# 17_FLOW_Sensor.net
KiCad netlist of a schematic drawn in Altium Designer
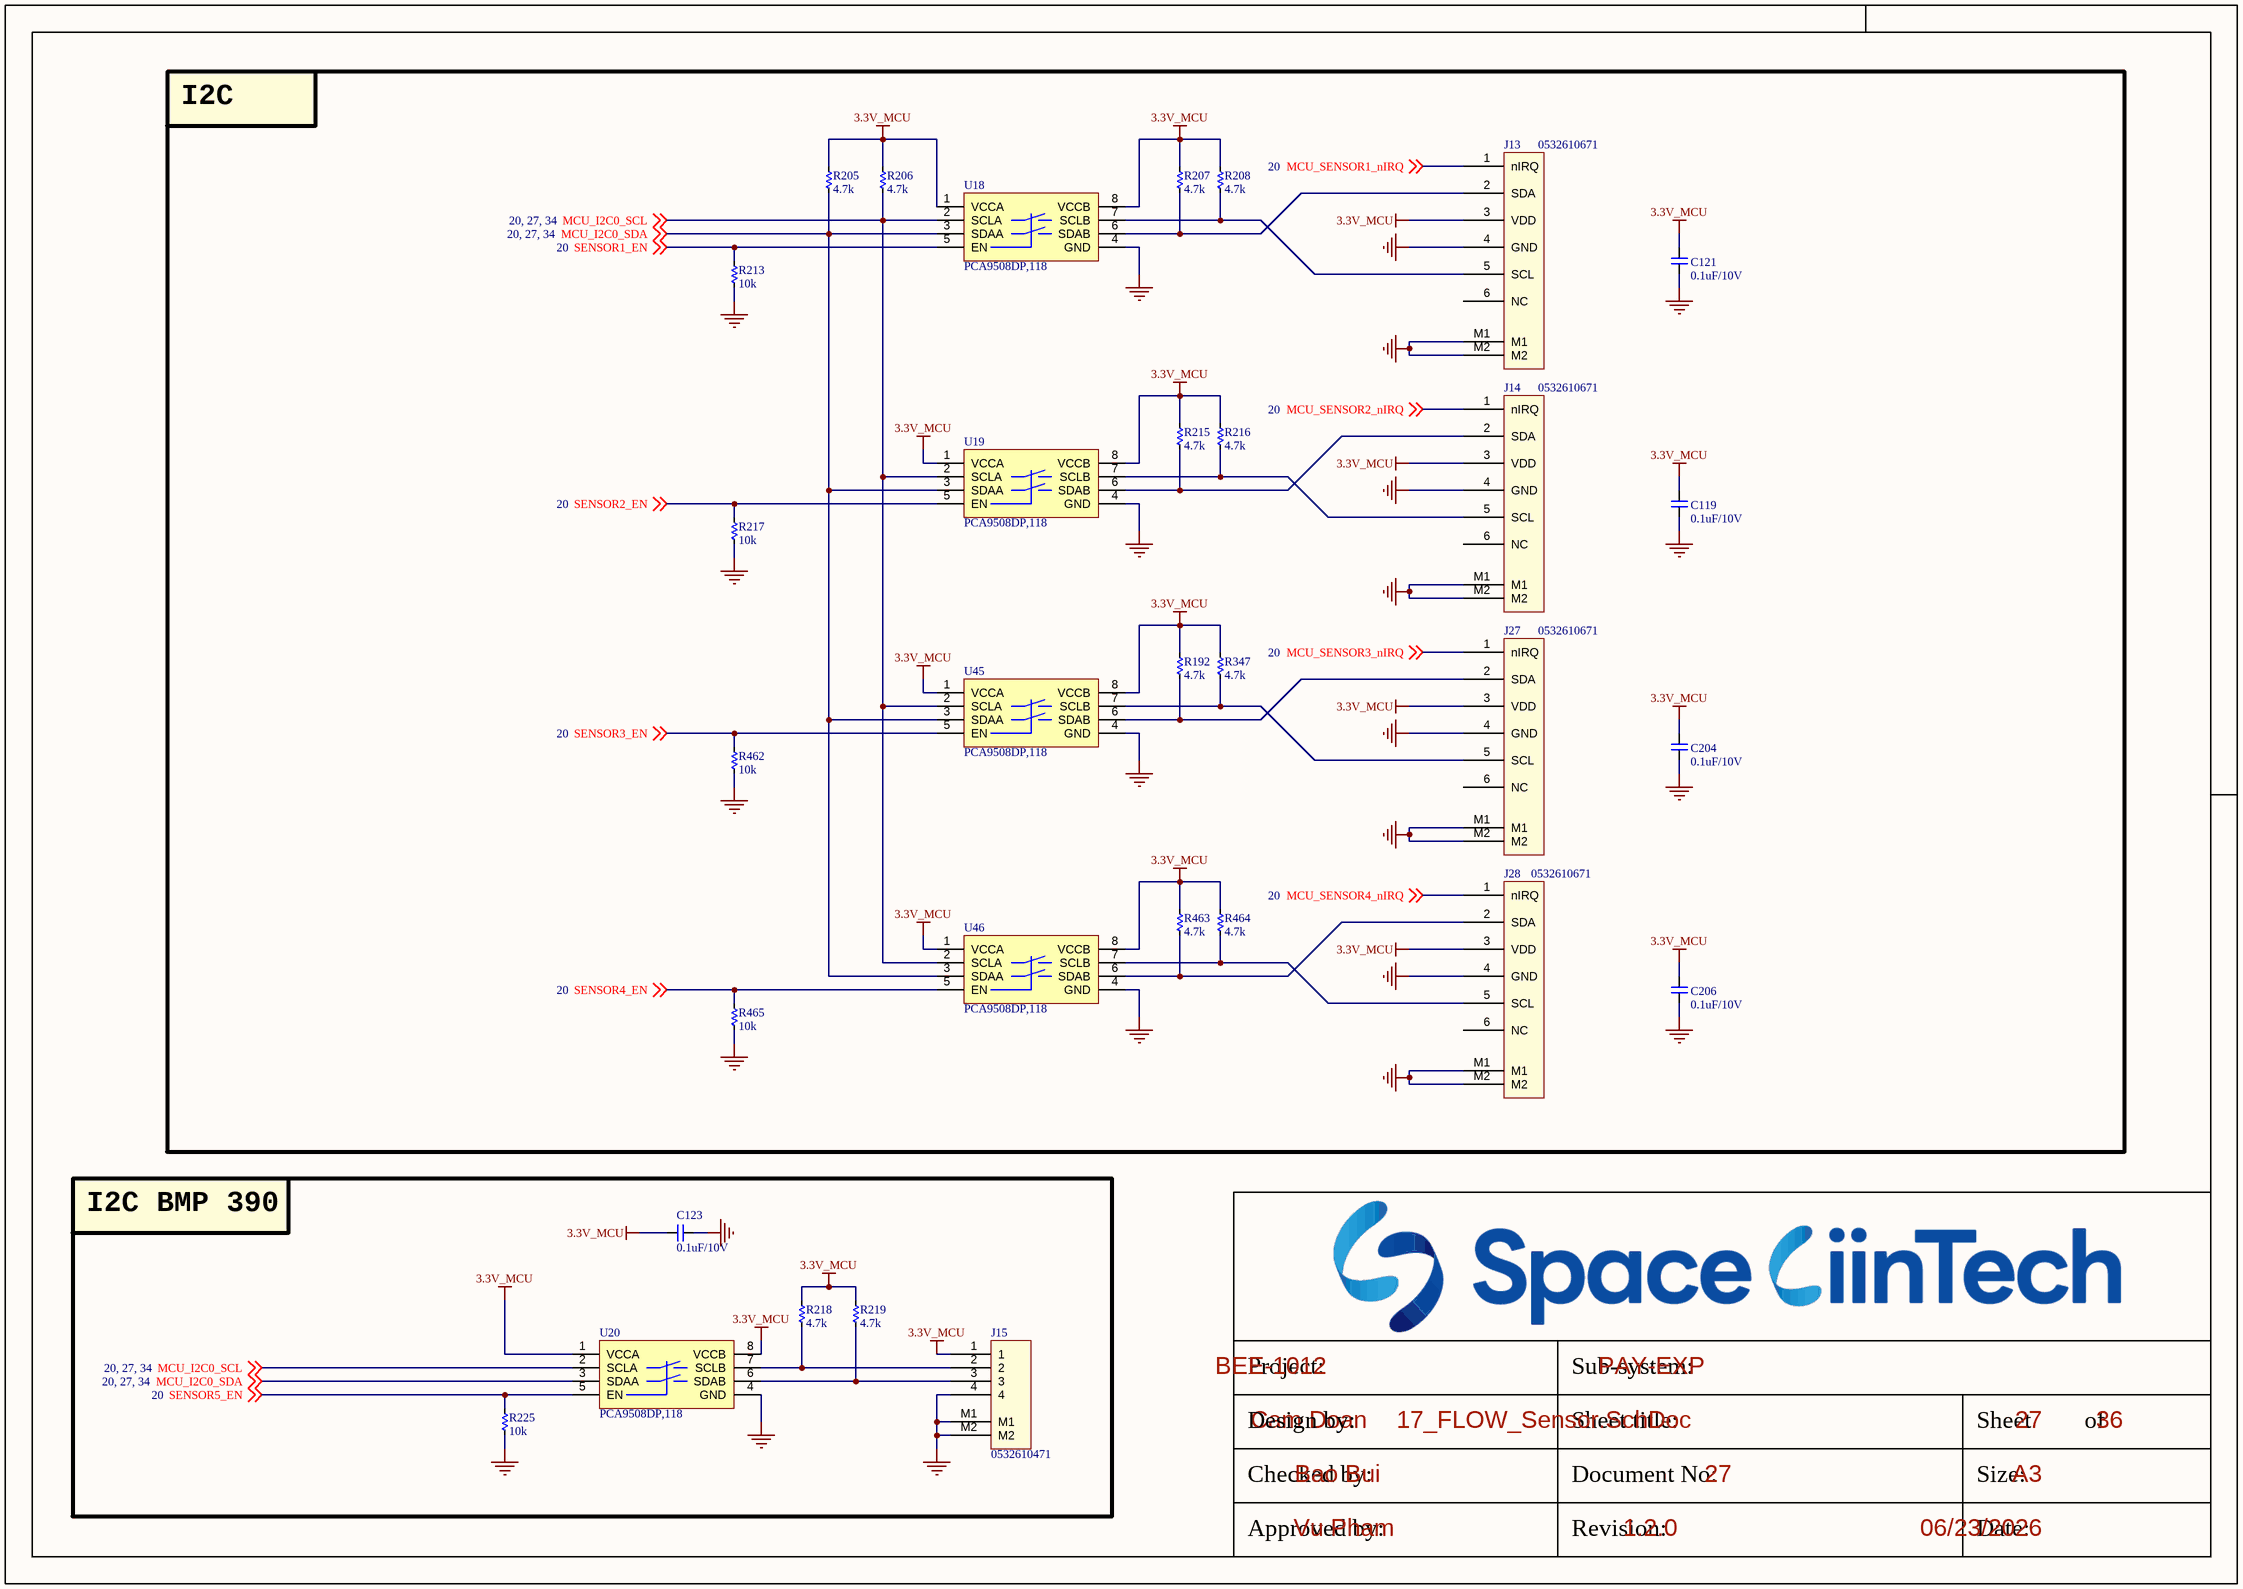
[diagram p0: 17_FLOW_Sensor.SchDoc]

(export (version "E")
  (design (tool "Eeschema 10.0.6"))
  (components
    (comp (ref "C119")
      (value "0.1uF/10V")
      (footprint "CAP_C_1005X60")
      (description "CAP")
      (libsource (lib "LABLIB") (part "_CAP_C_2"))
    )
    (comp (ref "C121")
      (value "0.1uF/10V")
      (footprint "CAP_C_1005X60")
      (description "CAP")
      (libsource (lib "LABLIB") (part "_CAP_C_2"))
    )
    (comp (ref "C123")
      (value "0.1uF/10V")
      (footprint "CAP_C_1005X60")
      (description "CAP")
      (libsource (lib "LABLIB") (part "_CAP_C_2"))
    )
    (comp (ref "C204")
      (value "0.1uF/10V")
      (footprint "CAP_C_1005X60")
      (description "CAP")
      (libsource (lib "LABLIB") (part "_CAP_C_2"))
    )
    (comp (ref "C206")
      (value "0.1uF/10V")
      (footprint "CAP_C_1005X60")
      (description "CAP")
      (libsource (lib "LABLIB") (part "_CAP_C_2"))
    )
    (comp (ref "J13")
      (value "0532610671")
      (footprint "MOLEX_0532610671")
      (libsource (lib "LABLIB") (part "FLOW_SENSOR"))
    )
    (comp (ref "J14")
      (value "0532610671")
      (footprint "MOLEX_0532610671")
      (libsource (lib "LABLIB") (part "FLOW_SENSOR"))
    )
    (comp (ref "J15")
      (value "0532610471")
      (footprint "MOLEX_0532610471")
      (libsource (lib "LABLIB") (part "Header 4x1_2M"))
    )
    (comp (ref "J27")
      (value "0532610671")
      (footprint "MOLEX_0532610671")
      (libsource (lib "LABLIB") (part "FLOW_SENSOR"))
    )
    (comp (ref "J28")
      (value "0532610671")
      (footprint "MOLEX_0532610671")
      (libsource (lib "LABLIB") (part "FLOW_SENSOR"))
    )
    (comp (ref "R192")
      (value "4.7k")
      (footprint "RES_C_1005X40")
      (description "RES")
      (libsource (lib "LABLIB") (part "_RES_B_2"))
    )
    (comp (ref "R205")
      (value "4.7k")
      (footprint "RES_C_1005X40")
      (description "RES")
      (libsource (lib "LABLIB") (part "_RES_B_2"))
    )
    (comp (ref "R206")
      (value "4.7k")
      (footprint "RES_C_1005X40")
      (description "RES")
      (libsource (lib "LABLIB") (part "_RES_B_2"))
    )
    (comp (ref "R207")
      (value "4.7k")
      (footprint "RES_C_1005X40")
      (description "RES")
      (libsource (lib "LABLIB") (part "_RES_B_2"))
    )
    (comp (ref "R208")
      (value "4.7k")
      (footprint "RES_C_1005X40")
      (description "RES")
      (libsource (lib "LABLIB") (part "_RES_B_2"))
    )
    (comp (ref "R213")
      (value "10k")
      (footprint "RES_C_1005X40")
      (description "RES")
      (libsource (lib "LABLIB") (part "_RES_B_2"))
    )
    (comp (ref "R215")
      (value "4.7k")
      (footprint "RES_C_1005X40")
      (description "RES")
      (libsource (lib "LABLIB") (part "_RES_B_2"))
    )
    (comp (ref "R216")
      (value "4.7k")
      (footprint "RES_C_1005X40")
      (description "RES")
      (libsource (lib "LABLIB") (part "_RES_B_2"))
    )
    (comp (ref "R217")
      (value "10k")
      (footprint "RES_C_1005X40")
      (description "RES")
      (libsource (lib "LABLIB") (part "_RES_B_2"))
    )
    (comp (ref "R218")
      (value "4.7k")
      (footprint "RES_C_1005X40")
      (description "RES")
      (libsource (lib "LABLIB") (part "_RES_B_2"))
    )
    (comp (ref "R219")
      (value "4.7k")
      (footprint "RES_C_1005X40")
      (description "RES")
      (libsource (lib "LABLIB") (part "_RES_B_2"))
    )
    (comp (ref "R225")
      (value "10k")
      (footprint "RES_C_1005X40")
      (description "RES")
      (libsource (lib "LABLIB") (part "_RES_B_2"))
    )
    (comp (ref "R347")
      (value "4.7k")
      (footprint "RES_C_1005X40")
      (description "RES")
      (libsource (lib "LABLIB") (part "_RES_B_2"))
    )
    (comp (ref "R462")
      (value "10k")
      (footprint "RES_C_1005X40")
      (description "RES")
      (libsource (lib "LABLIB") (part "_RES_B_2"))
    )
    (comp (ref "R463")
      (value "4.7k")
      (footprint "RES_C_1005X40")
      (description "RES")
      (libsource (lib "LABLIB") (part "_RES_B_2"))
    )
    (comp (ref "R464")
      (value "4.7k")
      (footprint "RES_C_1005X40")
      (description "RES")
      (libsource (lib "LABLIB") (part "_RES_B_2"))
    )
    (comp (ref "R465")
      (value "10k")
      (footprint "RES_C_1005X40")
      (description "RES")
      (libsource (lib "LABLIB") (part "_RES_B_2"))
    )
    (comp (ref "U18")
      (value "PCA9508DP,118")
      (footprint "TSOP8")
      (libsource (lib "EXP_HW_V3") (part "PCA9508DP,118"))
    )
    (comp (ref "U19")
      (value "PCA9508DP,118")
      (footprint "TSOP8")
      (libsource (lib "EXP_HW_V3") (part "PCA9508DP,118"))
    )
    (comp (ref "U20")
      (value "PCA9508DP,118")
      (footprint "TSOP8")
      (libsource (lib "EXP_HW_V3") (part "PCA9508DP,118"))
    )
    (comp (ref "U45")
      (value "PCA9508DP,118")
      (footprint "TSOP8")
      (libsource (lib "EXP_HW_V3") (part "PCA9508DP,118"))
    )
    (comp (ref "U46")
      (value "PCA9508DP,118")
      (footprint "TSOP8")
      (libsource (lib "EXP_HW_V3") (part "PCA9508DP,118"))
    )
  )
  (nets
    (net (code "1") (name "3.3V_MCU") (class "Default")
      (node (ref "C119") (pin "2") (pinfunction "2_2") (pintype "passive"))
      (node (ref "C121") (pin "2") (pinfunction "2_2") (pintype "passive"))
      (node (ref "C123") (pin "2") (pinfunction "2_2") (pintype "passive"))
      (node (ref "C204") (pin "2") (pinfunction "2_2") (pintype "passive"))
      (node (ref "C206") (pin "2") (pinfunction "2_2") (pintype "passive"))
      (node (ref "J13") (pin "3") (pinfunction "VDD_3") (pintype "passive"))
      (node (ref "J14") (pin "3") (pinfunction "VDD_3") (pintype "passive"))
      (node (ref "J15") (pin "1") (pinfunction "1_1") (pintype "passive"))
      (node (ref "J27") (pin "3") (pinfunction "VDD_3") (pintype "passive"))
      (node (ref "J28") (pin "3") (pinfunction "VDD_3") (pintype "passive"))
      (node (ref "R192") (pin "1") (pinfunction "1_1") (pintype "passive"))
      (node (ref "R205") (pin "1") (pinfunction "1_1") (pintype "passive"))
      (node (ref "R206") (pin "1") (pinfunction "1_1") (pintype "passive"))
      (node (ref "R207") (pin "1") (pinfunction "1_1") (pintype "passive"))
      (node (ref "R208") (pin "1") (pinfunction "1_1") (pintype "passive"))
      (node (ref "R215") (pin "1") (pinfunction "1_1") (pintype "passive"))
      (node (ref "R216") (pin "1") (pinfunction "1_1") (pintype "passive"))
      (node (ref "R218") (pin "1") (pinfunction "1_1") (pintype "passive"))
      (node (ref "R219") (pin "1") (pinfunction "1_1") (pintype "passive"))
      (node (ref "R347") (pin "1") (pinfunction "1_1") (pintype "passive"))
      (node (ref "R463") (pin "1") (pinfunction "1_1") (pintype "passive"))
      (node (ref "R464") (pin "1") (pinfunction "1_1") (pintype "passive"))
      (node (ref "U18") (pin "1") (pinfunction "VCCA_1") (pintype "passive"))
      (node (ref "U18") (pin "8") (pinfunction "VCCB_8") (pintype "passive"))
      (node (ref "U19") (pin "1") (pinfunction "VCCA_1") (pintype "passive"))
      (node (ref "U19") (pin "8") (pinfunction "VCCB_8") (pintype "passive"))
      (node (ref "U20") (pin "1") (pinfunction "VCCA_1") (pintype "passive"))
      (node (ref "U20") (pin "8") (pinfunction "VCCB_8") (pintype "passive"))
      (node (ref "U45") (pin "1") (pinfunction "VCCA_1") (pintype "passive"))
      (node (ref "U45") (pin "8") (pinfunction "VCCB_8") (pintype "passive"))
      (node (ref "U46") (pin "1") (pinfunction "VCCA_1") (pintype "passive"))
      (node (ref "U46") (pin "8") (pinfunction "VCCB_8") (pintype "passive"))
    )
    (net (code "2") (name "GND") (class "Default")
      (node (ref "C119") (pin "1") (pinfunction "1_1") (pintype "passive"))
      (node (ref "C121") (pin "1") (pinfunction "1_1") (pintype "passive"))
      (node (ref "C123") (pin "1") (pinfunction "1_1") (pintype "passive"))
      (node (ref "C204") (pin "1") (pinfunction "1_1") (pintype "passive"))
      (node (ref "C206") (pin "1") (pinfunction "1_1") (pintype "passive"))
      (node (ref "J13") (pin "4") (pinfunction "GND_4") (pintype "passive"))
      (node (ref "J13") (pin "M1") (pinfunction "M1_M1") (pintype "passive"))
      (node (ref "J13") (pin "M2") (pinfunction "M2_M2") (pintype "passive"))
      (node (ref "J14") (pin "4") (pinfunction "GND_4") (pintype "passive"))
      (node (ref "J14") (pin "M1") (pinfunction "M1_M1") (pintype "passive"))
      (node (ref "J14") (pin "M2") (pinfunction "M2_M2") (pintype "passive"))
      (node (ref "J15") (pin "4") (pinfunction "4_4") (pintype "passive"))
      (node (ref "J15") (pin "M1") (pinfunction "M1_M1") (pintype "passive"))
      (node (ref "J15") (pin "M2") (pinfunction "M2_M2") (pintype "passive"))
      (node (ref "J27") (pin "4") (pinfunction "GND_4") (pintype "passive"))
      (node (ref "J27") (pin "M1") (pinfunction "M1_M1") (pintype "passive"))
      (node (ref "J27") (pin "M2") (pinfunction "M2_M2") (pintype "passive"))
      (node (ref "J28") (pin "4") (pinfunction "GND_4") (pintype "passive"))
      (node (ref "J28") (pin "M1") (pinfunction "M1_M1") (pintype "passive"))
      (node (ref "J28") (pin "M2") (pinfunction "M2_M2") (pintype "passive"))
      (node (ref "R213") (pin "2") (pinfunction "2_2") (pintype "passive"))
      (node (ref "R217") (pin "2") (pinfunction "2_2") (pintype "passive"))
      (node (ref "R225") (pin "2") (pinfunction "2_2") (pintype "passive"))
      (node (ref "R462") (pin "2") (pinfunction "2_2") (pintype "passive"))
      (node (ref "R465") (pin "2") (pinfunction "2_2") (pintype "passive"))
      (node (ref "U18") (pin "4") (pinfunction "GND_4") (pintype "passive"))
      (node (ref "U19") (pin "4") (pinfunction "GND_4") (pintype "passive"))
      (node (ref "U20") (pin "4") (pinfunction "GND_4") (pintype "passive"))
      (node (ref "U45") (pin "4") (pinfunction "GND_4") (pintype "passive"))
      (node (ref "U46") (pin "4") (pinfunction "GND_4") (pintype "passive"))
    )
    (net (code "3") (name "MCU_I2C0_SCL") (class "Default")
      (node (ref "R206") (pin "2") (pinfunction "2_2") (pintype "passive"))
      (node (ref "U18") (pin "2") (pinfunction "SCLA_2") (pintype "passive"))
      (node (ref "U19") (pin "2") (pinfunction "SCLA_2") (pintype "passive"))
      (node (ref "U20") (pin "2") (pinfunction "SCLA_2") (pintype "passive"))
      (node (ref "U45") (pin "2") (pinfunction "SCLA_2") (pintype "passive"))
      (node (ref "U46") (pin "2") (pinfunction "SCLA_2") (pintype "passive"))
    )
    (net (code "4") (name "MCU_I2C0_SDA") (class "Default")
      (node (ref "R205") (pin "2") (pinfunction "2_2") (pintype "passive"))
      (node (ref "U18") (pin "3") (pinfunction "SDAA_3") (pintype "passive"))
      (node (ref "U19") (pin "3") (pinfunction "SDAA_3") (pintype "passive"))
      (node (ref "U20") (pin "3") (pinfunction "SDAA_3") (pintype "passive"))
      (node (ref "U45") (pin "3") (pinfunction "SDAA_3") (pintype "passive"))
      (node (ref "U46") (pin "3") (pinfunction "SDAA_3") (pintype "passive"))
    )
    (net (code "5") (name "MCU_SENSOR1_nIRQ") (class "Default")
      (node (ref "J13") (pin "1") (pinfunction "nIRQ_1") (pintype "passive"))
    )
    (net (code "6") (name "MCU_SENSOR2_nIRQ") (class "Default")
      (node (ref "J14") (pin "1") (pinfunction "nIRQ_1") (pintype "passive"))
    )
    (net (code "7") (name "MCU_SENSOR3_nIRQ") (class "Default")
      (node (ref "J27") (pin "1") (pinfunction "nIRQ_1") (pintype "passive"))
    )
    (net (code "8") (name "MCU_SENSOR4_nIRQ") (class "Default")
      (node (ref "J28") (pin "1") (pinfunction "nIRQ_1") (pintype "passive"))
    )
    (net (code "9") (name "Net-(J13-SCL)") (class "Default")
      (node (ref "J13") (pin "5") (pinfunction "SCL_5") (pintype "passive"))
      (node (ref "R208") (pin "2") (pinfunction "2_2") (pintype "passive"))
      (node (ref "U18") (pin "7") (pinfunction "SCLB_7") (pintype "passive"))
    )
    (net (code "10") (name "Net-(J13-SDA)") (class "Default")
      (node (ref "J13") (pin "2") (pinfunction "SDA_2") (pintype "passive"))
      (node (ref "R207") (pin "2") (pinfunction "2_2") (pintype "passive"))
      (node (ref "U18") (pin "6") (pinfunction "SDAB_6") (pintype "passive"))
    )
    (net (code "11") (name "Net-(J14-SCL)") (class "Default")
      (node (ref "J14") (pin "5") (pinfunction "SCL_5") (pintype "passive"))
      (node (ref "R216") (pin "2") (pinfunction "2_2") (pintype "passive"))
      (node (ref "U19") (pin "7") (pinfunction "SCLB_7") (pintype "passive"))
    )
    (net (code "12") (name "Net-(J14-SDA)") (class "Default")
      (node (ref "J14") (pin "2") (pinfunction "SDA_2") (pintype "passive"))
      (node (ref "R215") (pin "2") (pinfunction "2_2") (pintype "passive"))
      (node (ref "U19") (pin "6") (pinfunction "SDAB_6") (pintype "passive"))
    )
    (net (code "13") (name "Net-(J27-SCL)") (class "Default")
      (node (ref "J27") (pin "5") (pinfunction "SCL_5") (pintype "passive"))
      (node (ref "R347") (pin "2") (pinfunction "2_2") (pintype "passive"))
      (node (ref "U45") (pin "7") (pinfunction "SCLB_7") (pintype "passive"))
    )
    (net (code "14") (name "Net-(J27-SDA)") (class "Default")
      (node (ref "J27") (pin "2") (pinfunction "SDA_2") (pintype "passive"))
      (node (ref "R192") (pin "2") (pinfunction "2_2") (pintype "passive"))
      (node (ref "U45") (pin "6") (pinfunction "SDAB_6") (pintype "passive"))
    )
    (net (code "15") (name "Net-(J28-SCL)") (class "Default")
      (node (ref "J28") (pin "5") (pinfunction "SCL_5") (pintype "passive"))
      (node (ref "R464") (pin "2") (pinfunction "2_2") (pintype "passive"))
      (node (ref "U46") (pin "7") (pinfunction "SCLB_7") (pintype "passive"))
    )
    (net (code "16") (name "Net-(J28-SDA)") (class "Default")
      (node (ref "J28") (pin "2") (pinfunction "SDA_2") (pintype "passive"))
      (node (ref "R463") (pin "2") (pinfunction "2_2") (pintype "passive"))
      (node (ref "U46") (pin "6") (pinfunction "SDAB_6") (pintype "passive"))
    )
    (net (code "17") (name "Net-(U20-SCLB)") (class "Default")
      (node (ref "J15") (pin "2") (pinfunction "2_2") (pintype "passive"))
      (node (ref "R218") (pin "2") (pinfunction "2_2") (pintype "passive"))
      (node (ref "U20") (pin "7") (pinfunction "SCLB_7") (pintype "passive"))
    )
    (net (code "18") (name "Net-(U20-SDAB)") (class "Default")
      (node (ref "J15") (pin "3") (pinfunction "3_3") (pintype "passive"))
      (node (ref "R219") (pin "2") (pinfunction "2_2") (pintype "passive"))
      (node (ref "U20") (pin "6") (pinfunction "SDAB_6") (pintype "passive"))
    )
    (net (code "19") (name "SENSOR1_EN") (class "Default")
      (node (ref "R213") (pin "1") (pinfunction "1_1") (pintype "passive"))
      (node (ref "U18") (pin "5") (pinfunction "EN_5") (pintype "passive"))
    )
    (net (code "20") (name "SENSOR2_EN") (class "Default")
      (node (ref "R217") (pin "1") (pinfunction "1_1") (pintype "passive"))
      (node (ref "U19") (pin "5") (pinfunction "EN_5") (pintype "passive"))
    )
    (net (code "21") (name "SENSOR3_EN") (class "Default")
      (node (ref "R462") (pin "1") (pinfunction "1_1") (pintype "passive"))
      (node (ref "U45") (pin "5") (pinfunction "EN_5") (pintype "passive"))
    )
    (net (code "22") (name "SENSOR4_EN") (class "Default")
      (node (ref "R465") (pin "1") (pinfunction "1_1") (pintype "passive"))
      (node (ref "U46") (pin "5") (pinfunction "EN_5") (pintype "passive"))
    )
    (net (code "23") (name "SENSOR5_EN") (class "Default")
      (node (ref "R225") (pin "1") (pinfunction "1_1") (pintype "passive"))
      (node (ref "U20") (pin "5") (pinfunction "EN_5") (pintype "passive"))
    )
    (net (code "24") (name "unconnected-(J13-NC-Pad6)") (class "Default")
      (node (ref "J13") (pin "6") (pinfunction "NC_6") (pintype "passive"))
    )
    (net (code "25") (name "unconnected-(J14-NC-Pad6)") (class "Default")
      (node (ref "J14") (pin "6") (pinfunction "NC_6") (pintype "passive"))
    )
    (net (code "26") (name "unconnected-(J27-NC-Pad6)") (class "Default")
      (node (ref "J27") (pin "6") (pinfunction "NC_6") (pintype "passive"))
    )
    (net (code "27") (name "unconnected-(J28-NC-Pad6)") (class "Default")
      (node (ref "J28") (pin "6") (pinfunction "NC_6") (pintype "passive"))
    )
  )
)
